# LCD1202_SMD_module.net
KiCad netlist of a schematic drawn in Altium Designer
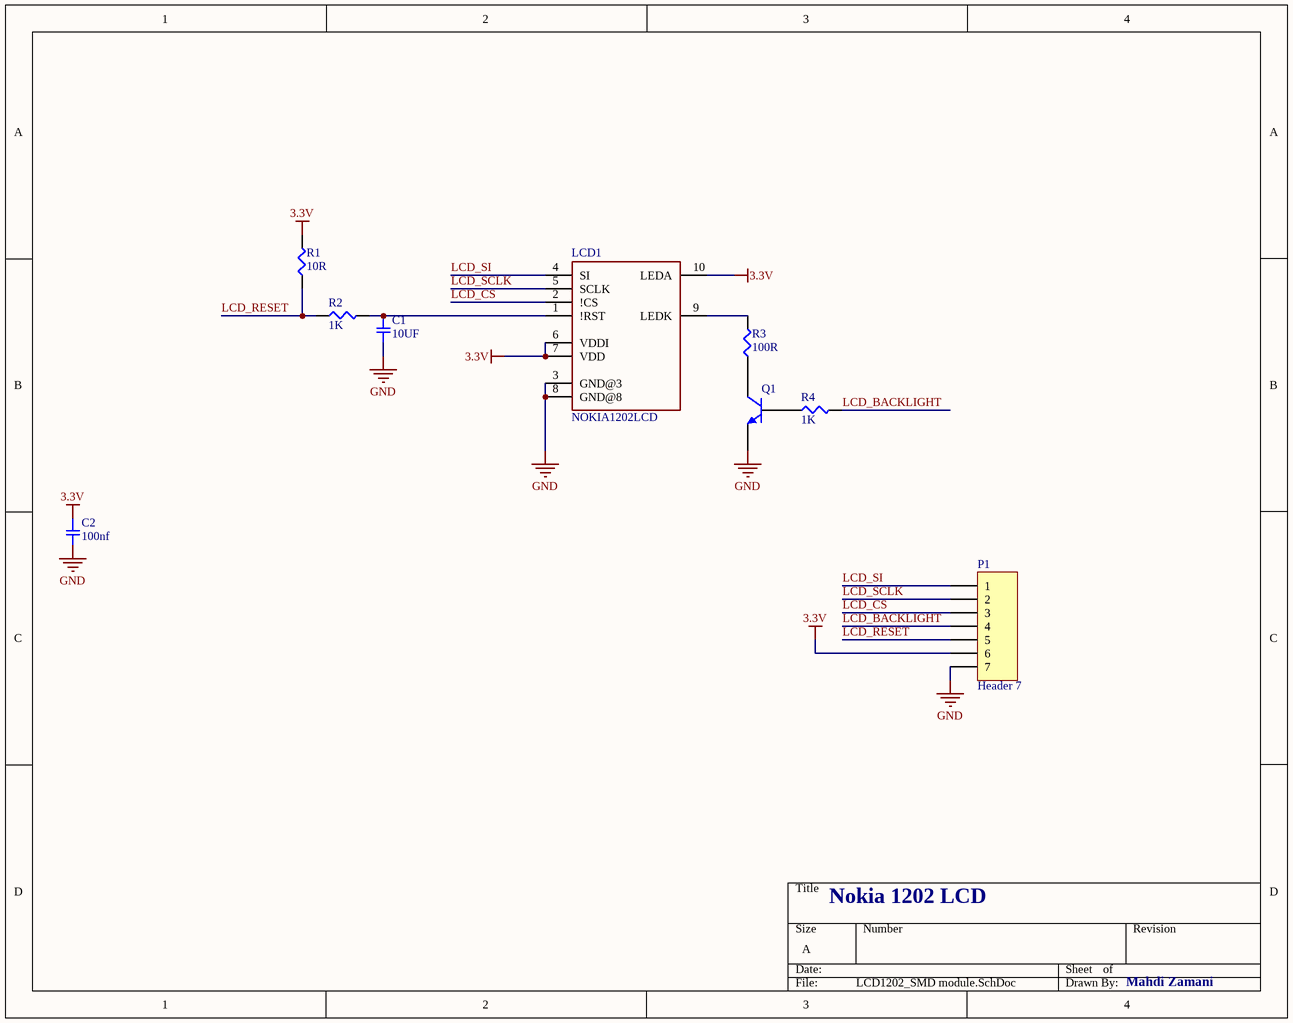
[diagram p0: LCD1202_SMD module.SchDoc]

(export (version "E")
  (design (tool "Eeschema 10.0.6"))
  (components
    (comp (ref "C1")
      (value "10UF")
      (footprint "SMD-0805C")
      (description "CAP CER 10000PF 250V X7T 0805")
      (fields
        (field (name "DIGI-KEY PART NUMBER") "490-13986-1-ND")
        (field (name "PART NUMBER") "GC321AD72E103KX01D")
      )
      (libsource (lib "capacitor_murata_0805") (part "GC321AD72E103KX01D"))
    )
    (comp (ref "C2")
      (value "100nf")
      (footprint "SMD-0805C")
      (description "CAP CER 10000PF 250V X7T 0805")
      (fields
        (field (name "DIGI-KEY PART NUMBER") "490-13986-1-ND")
        (field (name "PART NUMBER") "GC321AD72E103KX01D")
      )
      (libsource (lib "capacitor_murata_0805") (part "GC321AD72E103KX01D"))
    )
    (comp (ref "LCD1")
      (value "NOKIA1202LCD")
      (footprint "LCD 1202 right")
      (libsource (lib "MAD libs") (part "LCD1202-EXT"))
    )
    (comp (ref "P1")
      (value "Header 7")
      (footprint "SMD SOLDER CONNECTOR X7")
      (description "Header, 7-Pin")
      (fields (field (name "PUBLISHER") "Altium Limited"))
      (libsource (lib "Miscellaneous Connectors") (part "Header 7"))
    )
    (comp (ref "Q1")
      (value "BC817-25")
      (footprint "SOT23_BEC_M")
      (description "NPN General Purpose Amplifier")
      (fields (field (name "PUBLISHER") "Altium Limited"))
      (libsource (lib "MAIN") (part "BC817-25"))
    )
    (comp (ref "R1")
      (value "10R")
      (footprint "SMD-0805-RES")
      (description "RES SMD 1 OHM 1% 1/3W 0805")
      (fields (field (name "PART NUMBER") "ERJ-6BQF1R0V") (field (name "DIGI-KEY PART NUMBER") "P17499CT-ND"))
      (libsource (lib "Panasonic_ERJ_0805") (part "ERJ-6BQF1R0V"))
    )
    (comp (ref "R2")
      (value "1K")
      (footprint "SMD-0805-RES")
      (description "RES SMD 1 OHM 1% 1/3W 0805")
      (fields (field (name "PART NUMBER") "ERJ-6BQF1R0V") (field (name "DIGI-KEY PART NUMBER") "P17499CT-ND"))
      (libsource (lib "Panasonic_ERJ_0805") (part "ERJ-6BQF1R0V"))
    )
    (comp (ref "R3")
      (value "100R")
      (footprint "SMD-0805-RES")
      (description "RES SMD 1 OHM 1% 1/3W 0805")
      (fields (field (name "PART NUMBER") "ERJ-6BQF1R0V") (field (name "DIGI-KEY PART NUMBER") "P17499CT-ND"))
      (libsource (lib "Panasonic_ERJ_0805") (part "ERJ-6BQF1R0V"))
    )
    (comp (ref "R4")
      (value "1K")
      (footprint "SMD-0805-RES")
      (description "RES SMD 1 OHM 1% 1/3W 0805")
      (fields (field (name "PART NUMBER") "ERJ-6BQF1R0V") (field (name "DIGI-KEY PART NUMBER") "P17499CT-ND"))
      (libsource (lib "Panasonic_ERJ_0805") (part "ERJ-6BQF1R0V"))
    )
  )
  (nets
    (net (code "1") (name "/LCD_BACKLIGHT") (class "Default")
      (node (ref "P1") (pin "4") (pinfunction "4_4") (pintype "passive"))
      (node (ref "R4") (pin "2") (pinfunction "2_2") (pintype "passive"))
    )
    (net (code "2") (name "/LCD_CS") (class "Default")
      (node (ref "LCD1") (pin "2") (pinfunction "!CS_2") (pintype "passive"))
      (node (ref "P1") (pin "3") (pinfunction "3_3") (pintype "passive"))
    )
    (net (code "3") (name "/LCD_RESET") (class "Default")
      (node (ref "P1") (pin "5") (pinfunction "5_5") (pintype "passive"))
      (node (ref "R1") (pin "1") (pinfunction "1_1") (pintype "passive"))
      (node (ref "R2") (pin "1") (pinfunction "1_1") (pintype "passive"))
    )
    (net (code "4") (name "/LCD_SCLK") (class "Default")
      (node (ref "LCD1") (pin "5") (pinfunction "SCLK_5") (pintype "passive"))
      (node (ref "P1") (pin "2") (pinfunction "2_2") (pintype "passive"))
    )
    (net (code "5") (name "/LCD_SI") (class "Default")
      (node (ref "LCD1") (pin "4") (pinfunction "SI_4") (pintype "passive"))
      (node (ref "P1") (pin "1") (pinfunction "1_1") (pintype "passive"))
    )
    (net (code "6") (name "3.3V") (class "Default")
      (node (ref "C2") (pin "1") (pinfunction "1_1") (pintype "passive"))
      (node (ref "LCD1") (pin "10") (pinfunction "LEDA_10") (pintype "passive"))
      (node (ref "LCD1") (pin "6") (pinfunction "VDDI_6") (pintype "passive"))
      (node (ref "LCD1") (pin "7") (pinfunction "VDD_7") (pintype "passive"))
      (node (ref "P1") (pin "6") (pinfunction "6_6") (pintype "passive"))
      (node (ref "R1") (pin "2") (pinfunction "2_2") (pintype "passive"))
    )
    (net (code "7") (name "GND") (class "Default")
      (node (ref "C1") (pin "2") (pinfunction "2_2") (pintype "passive"))
      (node (ref "C2") (pin "2") (pinfunction "2_2") (pintype "passive"))
      (node (ref "LCD1") (pin "3") (pinfunction "GND@3_3") (pintype "passive"))
      (node (ref "LCD1") (pin "8") (pinfunction "GND@8_8") (pintype "passive"))
      (node (ref "P1") (pin "7") (pinfunction "7_7") (pintype "passive"))
      (node (ref "Q1") (pin "2") (pinfunction "E_2") (pintype "passive"))
    )
    (net (code "8") (name "Net-(LCD1-!RST)") (class "Default")
      (node (ref "C1") (pin "1") (pinfunction "1_1") (pintype "passive"))
      (node (ref "LCD1") (pin "1") (pinfunction "!RST_1") (pintype "passive"))
      (node (ref "R2") (pin "2") (pinfunction "2_2") (pintype "passive"))
    )
    (net (code "9") (name "Net-(LCD1-LEDK)") (class "Default")
      (node (ref "LCD1") (pin "9") (pinfunction "LEDK_9") (pintype "passive"))
      (node (ref "R3") (pin "2") (pinfunction "2_2") (pintype "passive"))
    )
    (net (code "10") (name "Net-(Q1-B)") (class "Default")
      (node (ref "Q1") (pin "1") (pinfunction "B_1") (pintype "passive"))
      (node (ref "R4") (pin "1") (pinfunction "1_1") (pintype "passive"))
    )
    (net (code "11") (name "Net-(Q1-C)") (class "Default")
      (node (ref "Q1") (pin "3") (pinfunction "C_3") (pintype "passive"))
      (node (ref "R3") (pin "1") (pinfunction "1_1") (pintype "passive"))
    )
  )
)
